# CustComp_0_9_SelfEtch.net
KiCad netlist of a schematic drawn in EAGLE
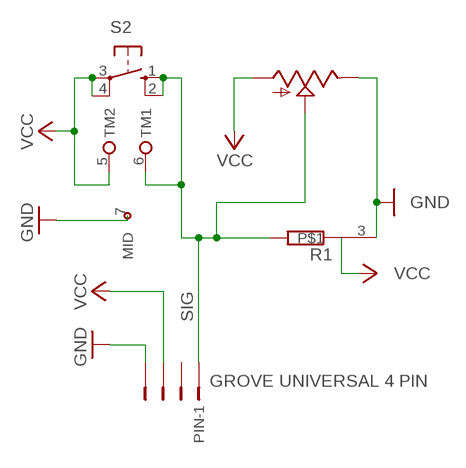
[diagram p0: schematic, sheet 1]

(export (version "E")
  (design (tool "Eeschema 10.0.6"))
  (components
    (comp (ref "PIN")
      (value "GROVE UNIVERSAL 4 PIN")
      (footprint "eagle-import:CON-JST_B4B-ZR")
      (fields (field (name "MF") "FARNELL") (field (name "MPN") "S4B-ZR(LF)(SN)"))
      (libsource (lib "eagle-import") (part "CON-JST_?4B-ZRB"))
    )
    (comp (ref "R1")
      (value "RES_PULL_UP_DOWNOPPOSING")
      (footprint "eagle-import:RES_PULL_UP_DOWN_OPPOSING")
      (libsource (lib "eagle-import") (part "RES_PULL_UP_DOWNOPPOSING"))
    )
    (comp (ref "S2")
      (value "TERMINAL_TAC_SWITCH")
      (footprint "eagle-import:TERMINAL_TACTILE-PTH")
      (libsource (lib "eagle-import") (part "TERMINAL_TAC_SWITCH"))
    )
    (comp (ref "U$1")
      (value "SPARKFUN_POT")
      (footprint "eagle-import:SPARKFUN_ALPS_POT")
      (libsource (lib "eagle-import") (part "SPARKFUN_POT"))
    )
  )
  (nets
    (net (code "1") (name "/SIG") (class "Default")
      (node (ref "PIN") (pin "1") (pinfunction "1_1") (pintype "passive"))
      (node (ref "R1") (pin "1") (pinfunction "2_1") (pintype "passive"))
      (node (ref "S2") (pin "1") (pinfunction "3_1") (pintype "passive"))
      (node (ref "S2") (pin "2") (pinfunction "4_2") (pintype "passive"))
      (node (ref "S2") (pin "6") (pinfunction "TM1_6") (pintype "bidirectional"))
      (node (ref "U$1") (pin "P$2") (pinfunction "S_P$2") (pintype "passive"))
    )
    (net (code "2") (name "GND") (class "Default")
      (node (ref "PIN") (pin "4") (pinfunction "1_4") (pintype "passive"))
      (node (ref "R1") (pin "3") (pinfunction "P$1_3") (pintype "bidirectional"))
      (node (ref "S2") (pin "7") (pinfunction "MID_7") (pintype "bidirectional"))
      (node (ref "U$1") (pin "P$1") (pinfunction "E_P$1") (pintype "passive"))
    )
    (net (code "3") (name "VCC") (class "Default")
      (node (ref "PIN") (pin "3") (pinfunction "1_3") (pintype "passive"))
      (node (ref "R1") (pin "2") (pinfunction "1_2") (pintype "passive"))
      (node (ref "S2") (pin "3") (pinfunction "1_3") (pintype "passive"))
      (node (ref "S2") (pin "4") (pinfunction "2_4") (pintype "passive"))
      (node (ref "S2") (pin "5") (pinfunction "TM2_5") (pintype "bidirectional"))
      (node (ref "U$1") (pin "P$3") (pinfunction "A_P$3") (pintype "passive"))
    )
    (net (code "4") (name "unconnected-(PINB-1-Pad2)") (class "Default")
      (node (ref "PIN") (pin "2") (pinfunction "1_2") (pintype "passive"))
    )
  )
)
